# temp-sensor-interface-hw.net
KiCad netlist of a schematic drawn in Altium Designer
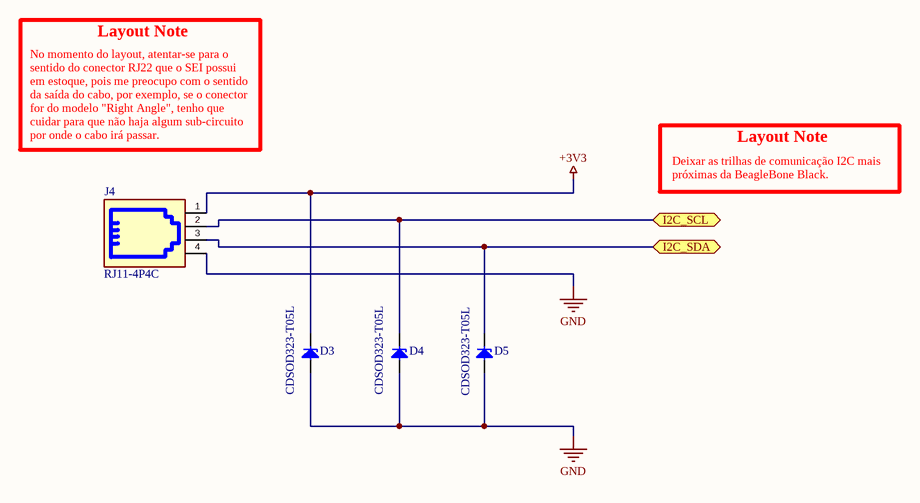
[diagram p0: temp-sensor-interface-hw.SchDoc]

(export (version "E")
  (design (tool "Eeschema 10.0.6"))
  (components
    (comp (ref "D3")
      (value "CDSOD323-T05L")
      (footprint "SOD-323")
      (description "Unidirectional TVS Diode")
      (libsource (lib "acopians-powerspy-monitoring-hw-library-schematic") (part "CDSOD323-T05L"))
    )
    (comp (ref "D4")
      (value "CDSOD323-T05L")
      (footprint "SOD-323")
      (description "Unidirectional TVS Diode")
      (libsource (lib "acopians-powerspy-monitoring-hw-library-schematic") (part "CDSOD323-T05L"))
    )
    (comp (ref "D5")
      (value "CDSOD323-T05L")
      (footprint "SOD-323")
      (description "Unidirectional TVS Diode")
      (libsource (lib "acopians-powerspy-monitoring-hw-library-schematic") (part "CDSOD323-T05L"))
    )
    (comp (ref "J4")
      (value "RJ11-4P4C")
      (footprint "YH55-01")
      (description "MC114268 JACK RJ11 4P4C PARA PLACA 14.5X10X12MM, CODIGO YH55-01, DAIER")
      (libsource (lib "acopians-powerspy-monitoring-hw-library-schematic") (part "RJ11"))
    )
  )
  (nets
    (net (code "1") (name "+3V3") (class "Default")
      (node (ref "D3") (pin "1") (pintype "passive"))
      (node (ref "J4") (pin "1") (pinfunction "1_1") (pintype "passive"))
    )
    (net (code "2") (name "/I2C_SCL") (class "Default")
      (node (ref "D4") (pin "1") (pintype "passive"))
      (node (ref "J4") (pin "2") (pinfunction "2_2") (pintype "passive"))
    )
    (net (code "3") (name "/I2C_SDA") (class "Default")
      (node (ref "D5") (pin "1") (pintype "passive"))
      (node (ref "J4") (pin "3") (pinfunction "3_3") (pintype "passive"))
    )
    (net (code "4") (name "GND") (class "Default")
      (node (ref "D3") (pin "2") (pintype "passive"))
      (node (ref "D4") (pin "2") (pintype "passive"))
      (node (ref "D5") (pin "2") (pintype "passive"))
      (node (ref "J4") (pin "4") (pinfunction "4_4") (pintype "passive"))
    )
  )
)
